# 2021_Deployment_REVB.net
KiCad netlist of a schematic drawn in EAGLE
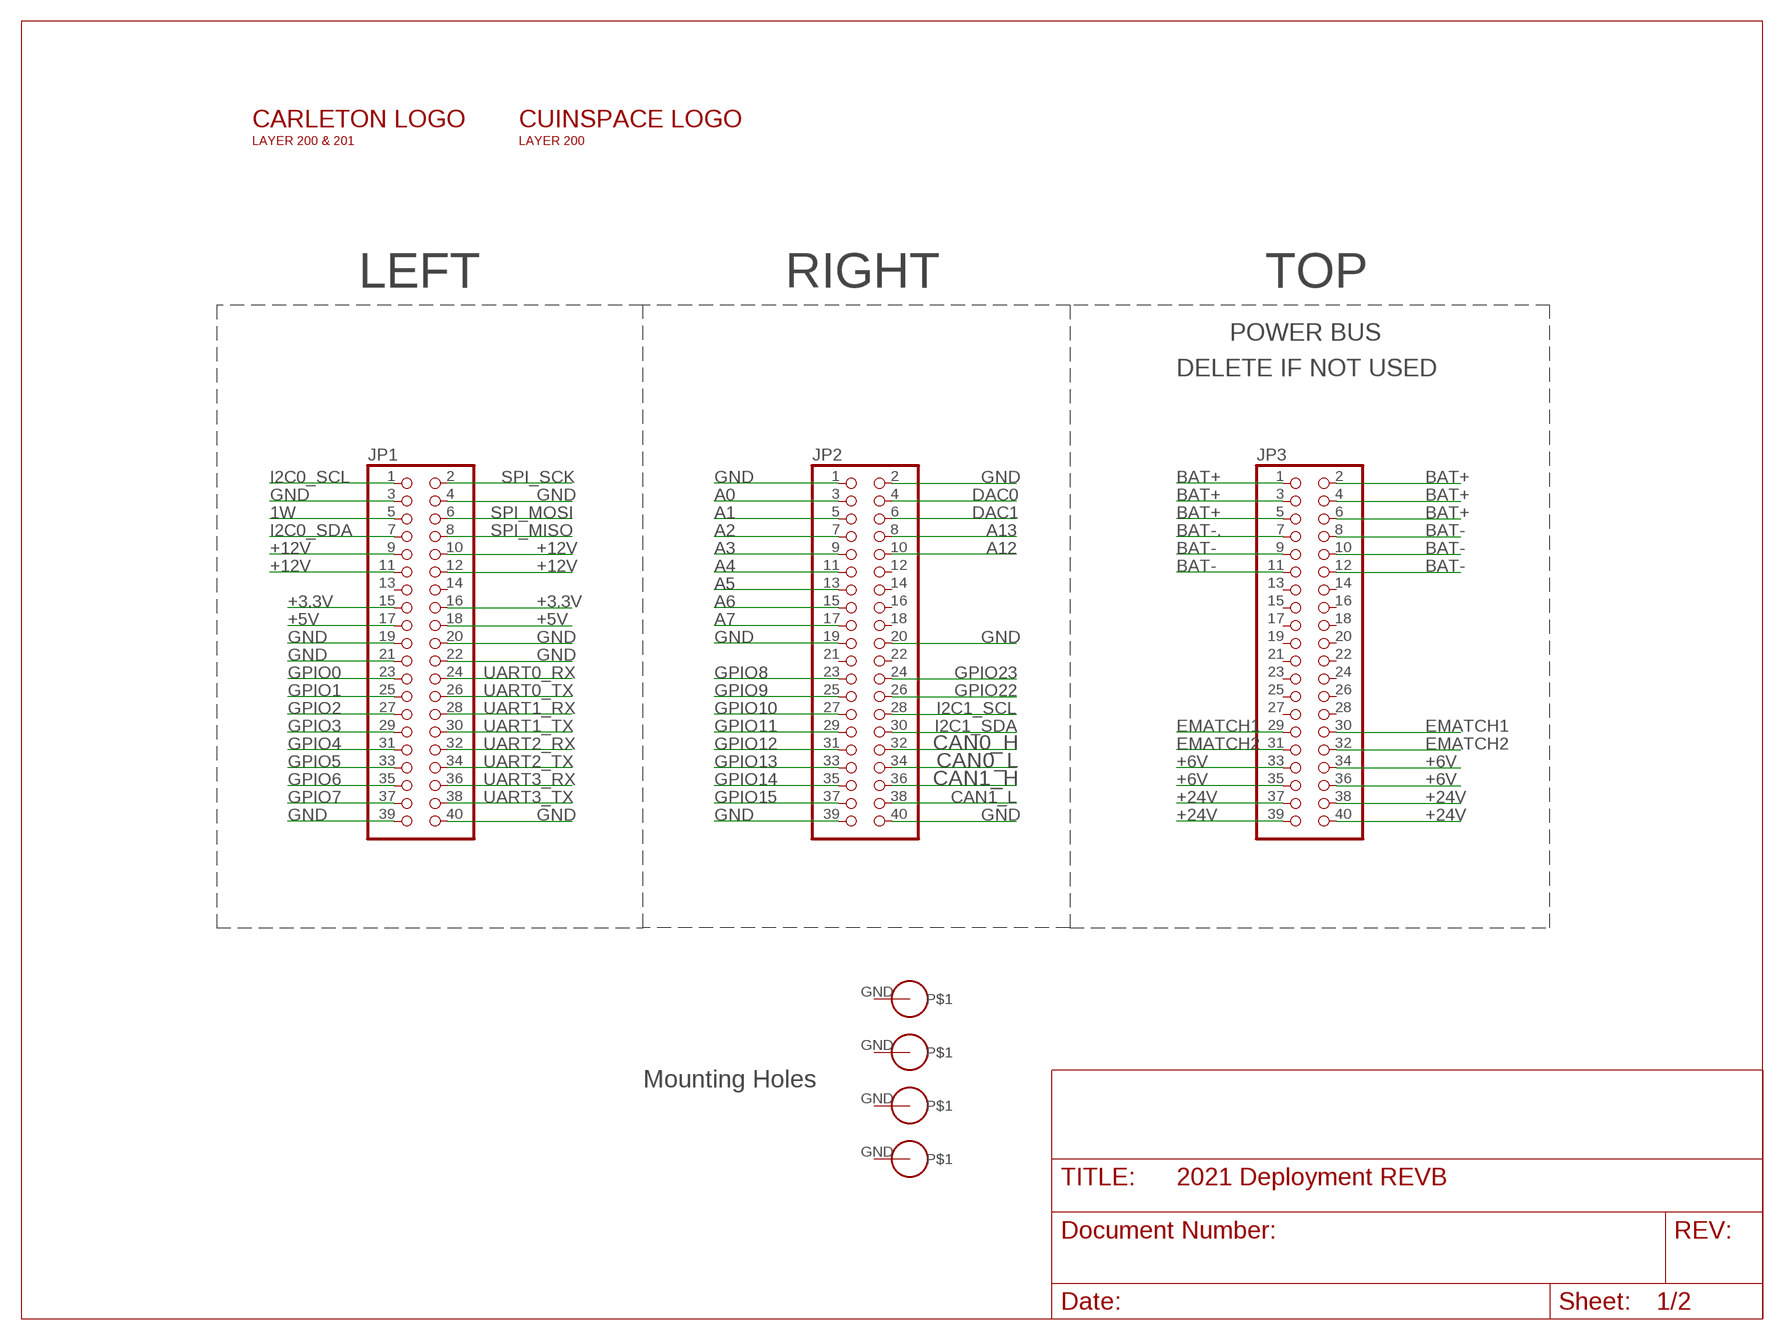
[diagram p0: schematic, sheet 1]
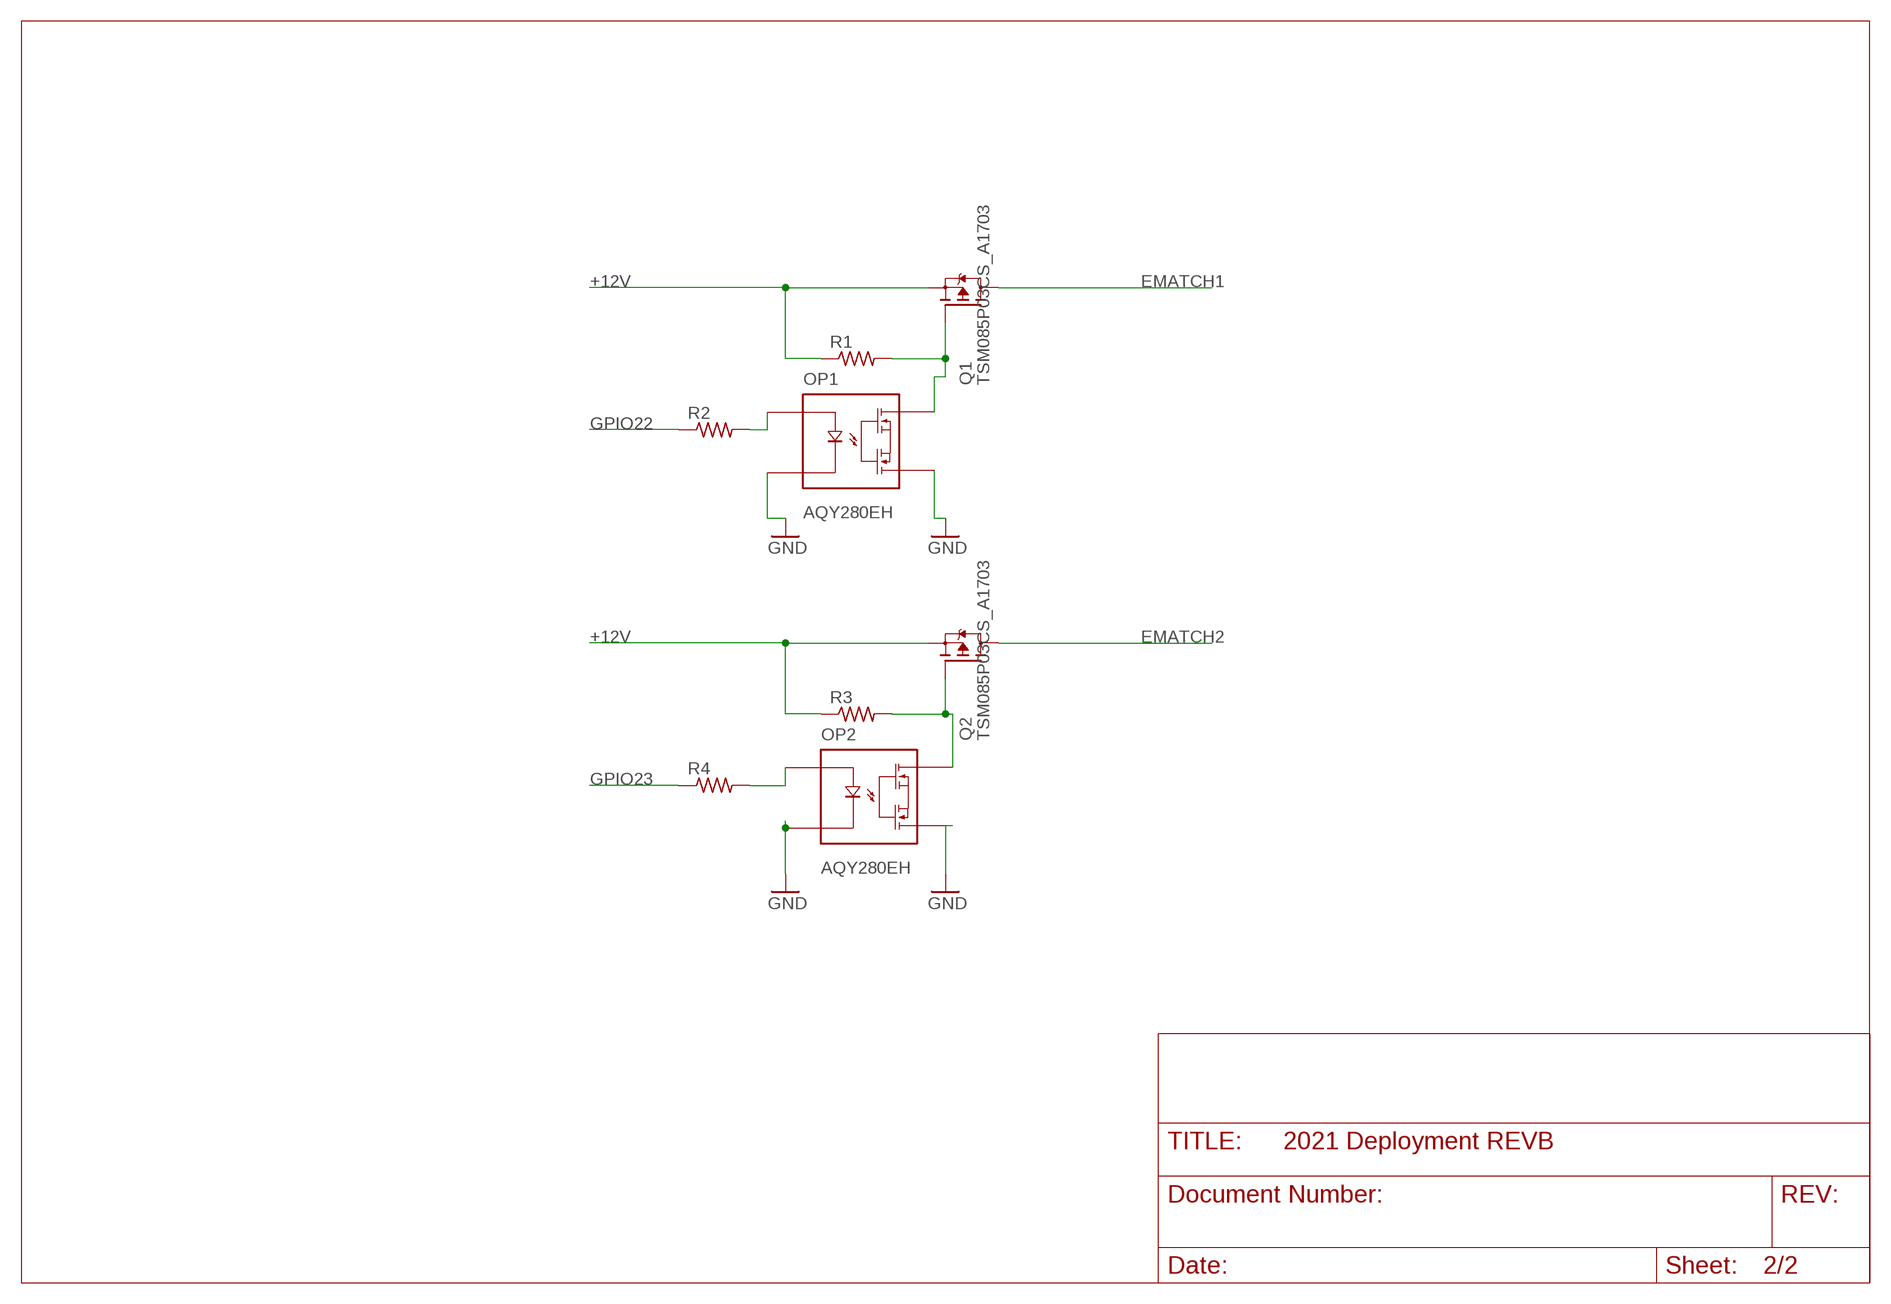
[diagram p1: schematic, sheet 2]

(export (version "E")
  (design (tool "Eeschema 10.0.6"))
  (components
    (comp (ref "OP1")
      (value "AQY280EH")
      (footprint "eagle-import:AQY280EH")
      (libsource (lib "eagle-import") (part "AQY280EH"))
    )
    (comp (ref "OP2")
      (value "AQY280EH")
      (footprint "eagle-import:AQY280EH")
      (libsource (lib "eagle-import") (part "AQY280EH"))
    )
    (comp (ref "Q1")
      (value "TSM085P03CS_A1703")
      (footprint "eagle-import:TSM085P03CS_A1703")
      (libsource (lib "eagle-import") (part "TSM085P03CS_A1703"))
    )
    (comp (ref "Q2")
      (value "TSM085P03CS_A1703")
      (footprint "eagle-import:TSM085P03CS_A1703")
      (libsource (lib "eagle-import") (part "TSM085P03CS_A1703"))
    )
    (comp (ref "R1")
      (value "R-US_R0805")
      (footprint "eagle-import:R0805")
      (libsource (lib "eagle-import") (part "R-US_R0805"))
    )
    (comp (ref "R2")
      (value "R-US_R0805")
      (footprint "eagle-import:R0805")
      (libsource (lib "eagle-import") (part "R-US_R0805"))
    )
    (comp (ref "R3")
      (value "R-US_R0805")
      (footprint "eagle-import:R0805")
      (libsource (lib "eagle-import") (part "R-US_R0805"))
    )
    (comp (ref "R4")
      (value "R-US_R0805")
      (footprint "eagle-import:R0805")
      (libsource (lib "eagle-import") (part "R-US_R0805"))
    )
    (comp (ref "$$U$1")
      (value "PS/104-MOUNTING-HOLE")
      (footprint "eagle-import:PC_104-MOUNTING-HOLE")
      (libsource (lib "eagle-import") (part "PS/104-MOUNTING-HOLE"))
    )
    (comp (ref "JP1")
      (value "PINHD-2X20")
      (footprint "eagle-import:2X20")
      (libsource (lib "eagle-import") (part "PINHD-2X20"))
    )
    (comp (ref "JP2")
      (value "PINHD-2X20")
      (footprint "eagle-import:2X20")
      (libsource (lib "eagle-import") (part "PINHD-2X20"))
    )
    (comp (ref "JP3")
      (value "PINHD-2X20")
      (footprint "eagle-import:2X20")
      (libsource (lib "eagle-import") (part "PINHD-2X20"))
    )
    (comp (ref "U$1")
      (value "PS/104-MOUNTING-HOLE")
      (footprint "eagle-import:PC_104-MOUNTING-HOLE")
      (libsource (lib "eagle-import") (part "PS/104-MOUNTING-HOLE"))
    )
    (comp (ref "U$2")
      (value "PS/104-MOUNTING-HOLE")
      (footprint "eagle-import:PC_104-MOUNTING-HOLE")
      (libsource (lib "eagle-import") (part "PS/104-MOUNTING-HOLE"))
    )
    (comp (ref "U$3")
      (value "PS/104-MOUNTING-HOLE")
      (footprint "eagle-import:PC_104-MOUNTING-HOLE")
      (libsource (lib "eagle-import") (part "PS/104-MOUNTING-HOLE"))
    )
    (comp (ref "U$4")
      (value "CARLETON3CM")
      (footprint "eagle-import:CARLETONU_3CM")
      (libsource (lib "eagle-import") (part "CARLETON3CM"))
    )
    (comp (ref "U$6")
      (value "INSPACE3CM_L")
      (footprint "eagle-import:INSPACE_3CM_LETTERS")
      (libsource (lib "eagle-import") (part "INSPACE3CM_L"))
    )
  )
  (nets
    (net (code "1") (name "+3.3V") (class "Default")
      (node (ref "JP1") (pin "15") (pinfunction "15_15") (pintype "passive"))
      (node (ref "JP1") (pin "16") (pinfunction "16_16") (pintype "passive"))
    )
    (net (code "2") (name "+5V") (class "Default")
      (node (ref "JP1") (pin "17") (pinfunction "17_17") (pintype "passive"))
      (node (ref "JP1") (pin "18") (pinfunction "18_18") (pintype "passive"))
    )
    (net (code "3") (name "+6V") (class "Default")
      (node (ref "JP3") (pin "33") (pinfunction "33_33") (pintype "passive"))
      (node (ref "JP3") (pin "34") (pinfunction "34_34") (pintype "passive"))
      (node (ref "JP3") (pin "35") (pinfunction "35_35") (pintype "passive"))
      (node (ref "JP3") (pin "36") (pinfunction "36_36") (pintype "passive"))
    )
    (net (code "4") (name "+12V") (class "Default")
      (node (ref "JP1") (pin "10") (pinfunction "10_10") (pintype "passive"))
      (node (ref "JP1") (pin "11") (pinfunction "11_11") (pintype "passive"))
      (node (ref "JP1") (pin "12") (pinfunction "12_12") (pintype "passive"))
      (node (ref "JP1") (pin "9") (pinfunction "9_9") (pintype "passive"))
      (node (ref "Q1") (pin "PIN1") (pinfunction "S_PIN1") (pintype "passive"))
      (node (ref "Q1") (pin "PIN2") (pinfunction "S_PIN2") (pintype "passive"))
      (node (ref "Q1") (pin "PIN3") (pinfunction "S_PIN3") (pintype "passive"))
      (node (ref "Q2") (pin "PIN1") (pinfunction "S_PIN1") (pintype "passive"))
      (node (ref "Q2") (pin "PIN2") (pinfunction "S_PIN2") (pintype "passive"))
      (node (ref "Q2") (pin "PIN3") (pinfunction "S_PIN3") (pintype "passive"))
      (node (ref "R1") (pin "1") (pinfunction "1_1") (pintype "passive"))
      (node (ref "R3") (pin "1") (pinfunction "1_1") (pintype "passive"))
    )
    (net (code "5") (name "+24V") (class "Default")
      (node (ref "JP3") (pin "37") (pinfunction "37_37") (pintype "passive"))
      (node (ref "JP3") (pin "38") (pinfunction "38_38") (pintype "passive"))
      (node (ref "JP3") (pin "39") (pinfunction "39_39") (pintype "passive"))
      (node (ref "JP3") (pin "40") (pinfunction "40_40") (pintype "passive"))
    )
    (net (code "6") (name "1W") (class "Default")
      (node (ref "JP1") (pin "5") (pinfunction "5_5") (pintype "passive"))
    )
    (net (code "7") (name "A0") (class "Default")
      (node (ref "JP2") (pin "3") (pinfunction "3_3") (pintype "passive"))
    )
    (net (code "8") (name "A1") (class "Default")
      (node (ref "JP2") (pin "5") (pinfunction "5_5") (pintype "passive"))
    )
    (net (code "9") (name "A2") (class "Default")
      (node (ref "JP2") (pin "7") (pinfunction "7_7") (pintype "passive"))
    )
    (net (code "10") (name "A3") (class "Default")
      (node (ref "JP2") (pin "9") (pinfunction "9_9") (pintype "passive"))
    )
    (net (code "11") (name "A4") (class "Default")
      (node (ref "JP2") (pin "11") (pinfunction "11_11") (pintype "passive"))
    )
    (net (code "12") (name "A5") (class "Default")
      (node (ref "JP2") (pin "13") (pinfunction "13_13") (pintype "passive"))
    )
    (net (code "13") (name "A6") (class "Default")
      (node (ref "JP2") (pin "15") (pinfunction "15_15") (pintype "passive"))
    )
    (net (code "14") (name "A7") (class "Default")
      (node (ref "JP2") (pin "17") (pinfunction "17_17") (pintype "passive"))
    )
    (net (code "15") (name "A12") (class "Default")
      (node (ref "JP2") (pin "10") (pinfunction "10_10") (pintype "passive"))
    )
    (net (code "16") (name "A13") (class "Default")
      (node (ref "JP2") (pin "8") (pinfunction "8_8") (pintype "passive"))
    )
    (net (code "17") (name "BAT+") (class "Default")
      (node (ref "JP3") (pin "1") (pinfunction "1_1") (pintype "passive"))
      (node (ref "JP3") (pin "2") (pinfunction "2_2") (pintype "passive"))
      (node (ref "JP3") (pin "3") (pinfunction "3_3") (pintype "passive"))
      (node (ref "JP3") (pin "4") (pinfunction "4_4") (pintype "passive"))
      (node (ref "JP3") (pin "5") (pinfunction "5_5") (pintype "passive"))
      (node (ref "JP3") (pin "6") (pinfunction "6_6") (pintype "passive"))
    )
    (net (code "18") (name "BAT-") (class "Default")
      (node (ref "JP3") (pin "10") (pinfunction "10_10") (pintype "passive"))
      (node (ref "JP3") (pin "11") (pinfunction "11_11") (pintype "passive"))
      (node (ref "JP3") (pin "12") (pinfunction "12_12") (pintype "passive"))
      (node (ref "JP3") (pin "8") (pinfunction "8_8") (pintype "passive"))
      (node (ref "JP3") (pin "9") (pinfunction "9_9") (pintype "passive"))
    )
    (net (code "19") (name "BAT-.") (class "Default")
      (node (ref "JP3") (pin "7") (pinfunction "7_7") (pintype "passive"))
    )
    (net (code "20") (name "CAN0_H") (class "Default")
      (node (ref "JP2") (pin "32") (pinfunction "32_32") (pintype "passive"))
    )
    (net (code "21") (name "CAN0_L") (class "Default")
      (node (ref "JP2") (pin "34") (pinfunction "34_34") (pintype "passive"))
    )
    (net (code "22") (name "CAN1_H") (class "Default")
      (node (ref "JP2") (pin "36") (pinfunction "36_36") (pintype "passive"))
    )
    (net (code "23") (name "CAN1_L") (class "Default")
      (node (ref "JP2") (pin "38") (pinfunction "38_38") (pintype "passive"))
    )
    (net (code "24") (name "DAC0") (class "Default")
      (node (ref "JP2") (pin "4") (pinfunction "4_4") (pintype "passive"))
    )
    (net (code "25") (name "DAC1") (class "Default")
      (node (ref "JP2") (pin "6") (pinfunction "6_6") (pintype "passive"))
    )
    (net (code "26") (name "EMATCH1") (class "Default")
      (node (ref "JP3") (pin "29") (pinfunction "29_29") (pintype "passive"))
      (node (ref "JP3") (pin "30") (pinfunction "30_30") (pintype "passive"))
      (node (ref "Q1") (pin "PIN5") (pinfunction "D_PIN5") (pintype "passive"))
      (node (ref "Q1") (pin "PIN6") (pinfunction "D_PIN6") (pintype "passive"))
      (node (ref "Q1") (pin "PIN7") (pinfunction "D_PIN7") (pintype "passive"))
      (node (ref "Q1") (pin "PIN8") (pinfunction "D_PIN8") (pintype "passive"))
    )
    (net (code "27") (name "EMATCH2") (class "Default")
      (node (ref "JP3") (pin "31") (pinfunction "31_31") (pintype "passive"))
      (node (ref "JP3") (pin "32") (pinfunction "32_32") (pintype "passive"))
      (node (ref "Q2") (pin "PIN5") (pinfunction "D_PIN5") (pintype "passive"))
      (node (ref "Q2") (pin "PIN6") (pinfunction "D_PIN6") (pintype "passive"))
      (node (ref "Q2") (pin "PIN7") (pinfunction "D_PIN7") (pintype "passive"))
      (node (ref "Q2") (pin "PIN8") (pinfunction "D_PIN8") (pintype "passive"))
    )
    (net (code "28") (name "GND") (class "Default")
      (node (ref "JP1") (pin "19") (pinfunction "19_19") (pintype "passive"))
      (node (ref "JP1") (pin "20") (pinfunction "20_20") (pintype "passive"))
      (node (ref "JP1") (pin "21") (pinfunction "21_21") (pintype "passive"))
      (node (ref "JP1") (pin "22") (pinfunction "22_22") (pintype "passive"))
      (node (ref "JP1") (pin "3") (pinfunction "3_3") (pintype "passive"))
      (node (ref "JP1") (pin "39") (pinfunction "39_39") (pintype "passive"))
      (node (ref "JP1") (pin "4") (pinfunction "4_4") (pintype "passive"))
      (node (ref "JP1") (pin "40") (pinfunction "40_40") (pintype "passive"))
      (node (ref "JP2") (pin "1") (pinfunction "1_1") (pintype "passive"))
      (node (ref "JP2") (pin "19") (pinfunction "19_19") (pintype "passive"))
      (node (ref "JP2") (pin "2") (pinfunction "2_2") (pintype "passive"))
      (node (ref "JP2") (pin "20") (pinfunction "20_20") (pintype "passive"))
      (node (ref "JP2") (pin "39") (pinfunction "39_39") (pintype "passive"))
      (node (ref "JP2") (pin "40") (pinfunction "40_40") (pintype "passive"))
      (node (ref "OP1") (pin "PIN2") (pinfunction "C_PIN2") (pintype "bidirectional"))
      (node (ref "OP1") (pin "PIN3") (pinfunction "BOTTOM_PIN3") (pintype "bidirectional"))
      (node (ref "OP2") (pin "PIN2") (pinfunction "C_PIN2") (pintype "bidirectional"))
      (node (ref "OP2") (pin "PIN3") (pinfunction "BOTTOM_PIN3") (pintype "bidirectional"))
    )
    (net (code "29") (name "GPIO0") (class "Default")
      (node (ref "JP1") (pin "23") (pinfunction "23_23") (pintype "passive"))
    )
    (net (code "30") (name "GPIO1") (class "Default")
      (node (ref "JP1") (pin "25") (pinfunction "25_25") (pintype "passive"))
    )
    (net (code "31") (name "GPIO2") (class "Default")
      (node (ref "JP1") (pin "27") (pinfunction "27_27") (pintype "passive"))
    )
    (net (code "32") (name "GPIO3") (class "Default")
      (node (ref "JP1") (pin "29") (pinfunction "29_29") (pintype "passive"))
    )
    (net (code "33") (name "GPIO4") (class "Default")
      (node (ref "JP1") (pin "31") (pinfunction "31_31") (pintype "passive"))
    )
    (net (code "34") (name "GPIO5") (class "Default")
      (node (ref "JP1") (pin "33") (pinfunction "33_33") (pintype "passive"))
    )
    (net (code "35") (name "GPIO6") (class "Default")
      (node (ref "JP1") (pin "35") (pinfunction "35_35") (pintype "passive"))
    )
    (net (code "36") (name "GPIO7") (class "Default")
      (node (ref "JP1") (pin "37") (pinfunction "37_37") (pintype "passive"))
    )
    (net (code "37") (name "GPIO8") (class "Default")
      (node (ref "JP2") (pin "23") (pinfunction "23_23") (pintype "passive"))
    )
    (net (code "38") (name "GPIO9") (class "Default")
      (node (ref "JP2") (pin "25") (pinfunction "25_25") (pintype "passive"))
    )
    (net (code "39") (name "GPIO10") (class "Default")
      (node (ref "JP2") (pin "27") (pinfunction "27_27") (pintype "passive"))
    )
    (net (code "40") (name "GPIO11") (class "Default")
      (node (ref "JP2") (pin "29") (pinfunction "29_29") (pintype "passive"))
    )
    (net (code "41") (name "GPIO12") (class "Default")
      (node (ref "JP2") (pin "31") (pinfunction "31_31") (pintype "passive"))
    )
    (net (code "42") (name "GPIO13") (class "Default")
      (node (ref "JP2") (pin "33") (pinfunction "33_33") (pintype "passive"))
    )
    (net (code "43") (name "GPIO14") (class "Default")
      (node (ref "JP2") (pin "35") (pinfunction "35_35") (pintype "passive"))
    )
    (net (code "44") (name "GPIO15") (class "Default")
      (node (ref "JP2") (pin "37") (pinfunction "37_37") (pintype "passive"))
    )
    (net (code "45") (name "GPIO22") (class "Default")
      (node (ref "JP2") (pin "26") (pinfunction "26_26") (pintype "passive"))
      (node (ref "R2") (pin "1") (pinfunction "1_1") (pintype "passive"))
    )
    (net (code "46") (name "GPIO23") (class "Default")
      (node (ref "JP2") (pin "24") (pinfunction "24_24") (pintype "passive"))
      (node (ref "R4") (pin "1") (pinfunction "1_1") (pintype "passive"))
    )
    (net (code "47") (name "I2C0_SCL") (class "Default")
      (node (ref "JP1") (pin "1") (pinfunction "1_1") (pintype "passive"))
    )
    (net (code "48") (name "I2C0_SDA") (class "Default")
      (node (ref "JP1") (pin "7") (pinfunction "7_7") (pintype "passive"))
    )
    (net (code "49") (name "I2C1_SCL") (class "Default")
      (node (ref "JP2") (pin "28") (pinfunction "28_28") (pintype "passive"))
    )
    (net (code "50") (name "I2C1_SDA") (class "Default")
      (node (ref "JP2") (pin "30") (pinfunction "30_30") (pintype "passive"))
    )
    (net (code "51") (name "Net-(OP1-A)") (class "Default")
      (node (ref "OP1") (pin "PIN1") (pinfunction "A_PIN1") (pintype "bidirectional"))
      (node (ref "R2") (pin "2") (pinfunction "2_2") (pintype "passive"))
    )
    (net (code "52") (name "Net-(OP1-TOP)") (class "Default")
      (node (ref "OP1") (pin "PIN4") (pinfunction "TOP_PIN4") (pintype "bidirectional"))
      (node (ref "Q1") (pin "PIN4") (pinfunction "G_PIN4") (pintype "passive"))
      (node (ref "R1") (pin "2") (pinfunction "2_2") (pintype "passive"))
    )
    (net (code "53") (name "Net-(OP2-A)") (class "Default")
      (node (ref "OP2") (pin "PIN1") (pinfunction "A_PIN1") (pintype "bidirectional"))
      (node (ref "R4") (pin "2") (pinfunction "2_2") (pintype "passive"))
    )
    (net (code "54") (name "Net-(OP2-TOP)") (class "Default")
      (node (ref "OP2") (pin "PIN4") (pinfunction "TOP_PIN4") (pintype "bidirectional"))
      (node (ref "Q2") (pin "PIN4") (pinfunction "G_PIN4") (pintype "passive"))
      (node (ref "R3") (pin "2") (pinfunction "2_2") (pintype "passive"))
    )
    (net (code "55") (name "SPI_MISO") (class "Default")
      (node (ref "JP1") (pin "8") (pinfunction "8_8") (pintype "passive"))
    )
    (net (code "56") (name "SPI_MOSI") (class "Default")
      (node (ref "JP1") (pin "6") (pinfunction "6_6") (pintype "passive"))
    )
    (net (code "57") (name "SPI_SCK") (class "Default")
      (node (ref "JP1") (pin "2") (pinfunction "2_2") (pintype "passive"))
    )
    (net (code "58") (name "UART0_RX") (class "Default")
      (node (ref "JP1") (pin "24") (pinfunction "24_24") (pintype "passive"))
    )
    (net (code "59") (name "UART0_TX") (class "Default")
      (node (ref "JP1") (pin "26") (pinfunction "26_26") (pintype "passive"))
    )
    (net (code "60") (name "UART1_RX") (class "Default")
      (node (ref "JP1") (pin "28") (pinfunction "28_28") (pintype "passive"))
    )
    (net (code "61") (name "UART1_TX") (class "Default")
      (node (ref "JP1") (pin "30") (pinfunction "30_30") (pintype "passive"))
    )
    (net (code "62") (name "UART2_RX") (class "Default")
      (node (ref "JP1") (pin "32") (pinfunction "32_32") (pintype "passive"))
    )
    (net (code "63") (name "UART2_TX") (class "Default")
      (node (ref "JP1") (pin "34") (pinfunction "34_34") (pintype "passive"))
    )
    (net (code "64") (name "UART3_RX") (class "Default")
      (node (ref "JP1") (pin "36") (pinfunction "36_36") (pintype "passive"))
    )
    (net (code "65") (name "UART3_TX") (class "Default")
      (node (ref "JP1") (pin "38") (pinfunction "38_38") (pintype "passive"))
    )
    (net (code "66") (name "unconnected-($$U$1-P$1-PadGND)") (class "Default")
      (node (ref "$$U$1") (pin "GND") (pinfunction "P$1_GND") (pintype "bidirectional"))
    )
    (net (code "67") (name "unconnected-(JP1-Pad13)") (class "Default")
      (node (ref "JP1") (pin "13") (pinfunction "13_13") (pintype "passive"))
    )
    (net (code "68") (name "unconnected-(JP1-Pad14)") (class "Default")
      (node (ref "JP1") (pin "14") (pinfunction "14_14") (pintype "passive"))
    )
    (net (code "69") (name "unconnected-(JP2-Pad12)") (class "Default")
      (node (ref "JP2") (pin "12") (pinfunction "12_12") (pintype "passive"))
    )
    (net (code "70") (name "unconnected-(JP2-Pad14)") (class "Default")
      (node (ref "JP2") (pin "14") (pinfunction "14_14") (pintype "passive"))
    )
    (net (code "71") (name "unconnected-(JP2-Pad16)") (class "Default")
      (node (ref "JP2") (pin "16") (pinfunction "16_16") (pintype "passive"))
    )
    (net (code "72") (name "unconnected-(JP2-Pad18)") (class "Default")
      (node (ref "JP2") (pin "18") (pinfunction "18_18") (pintype "passive"))
    )
    (net (code "73") (name "unconnected-(JP2-Pad21)") (class "Default")
      (node (ref "JP2") (pin "21") (pinfunction "21_21") (pintype "passive"))
    )
    (net (code "74") (name "unconnected-(JP2-Pad22)") (class "Default")
      (node (ref "JP2") (pin "22") (pinfunction "22_22") (pintype "passive"))
    )
    (net (code "75") (name "unconnected-(JP3-Pad13)") (class "Default")
      (node (ref "JP3") (pin "13") (pinfunction "13_13") (pintype "passive"))
    )
    (net (code "76") (name "unconnected-(JP3-Pad14)") (class "Default")
      (node (ref "JP3") (pin "14") (pinfunction "14_14") (pintype "passive"))
    )
    (net (code "77") (name "unconnected-(JP3-Pad15)") (class "Default")
      (node (ref "JP3") (pin "15") (pinfunction "15_15") (pintype "passive"))
    )
    (net (code "78") (name "unconnected-(JP3-Pad16)") (class "Default")
      (node (ref "JP3") (pin "16") (pinfunction "16_16") (pintype "passive"))
    )
    (net (code "79") (name "unconnected-(JP3-Pad17)") (class "Default")
      (node (ref "JP3") (pin "17") (pinfunction "17_17") (pintype "passive"))
    )
    (net (code "80") (name "unconnected-(JP3-Pad18)") (class "Default")
      (node (ref "JP3") (pin "18") (pinfunction "18_18") (pintype "passive"))
    )
    (net (code "81") (name "unconnected-(JP3-Pad19)") (class "Default")
      (node (ref "JP3") (pin "19") (pinfunction "19_19") (pintype "passive"))
    )
    (net (code "82") (name "unconnected-(JP3-Pad20)") (class "Default")
      (node (ref "JP3") (pin "20") (pinfunction "20_20") (pintype "passive"))
    )
    (net (code "83") (name "unconnected-(JP3-Pad21)") (class "Default")
      (node (ref "JP3") (pin "21") (pinfunction "21_21") (pintype "passive"))
    )
    (net (code "84") (name "unconnected-(JP3-Pad22)") (class "Default")
      (node (ref "JP3") (pin "22") (pinfunction "22_22") (pintype "passive"))
    )
    (net (code "85") (name "unconnected-(JP3-Pad23)") (class "Default")
      (node (ref "JP3") (pin "23") (pinfunction "23_23") (pintype "passive"))
    )
    (net (code "86") (name "unconnected-(JP3-Pad24)") (class "Default")
      (node (ref "JP3") (pin "24") (pinfunction "24_24") (pintype "passive"))
    )
    (net (code "87") (name "unconnected-(JP3-Pad25)") (class "Default")
      (node (ref "JP3") (pin "25") (pinfunction "25_25") (pintype "passive"))
    )
    (net (code "88") (name "unconnected-(JP3-Pad26)") (class "Default")
      (node (ref "JP3") (pin "26") (pinfunction "26_26") (pintype "passive"))
    )
    (net (code "89") (name "unconnected-(JP3-Pad27)") (class "Default")
      (node (ref "JP3") (pin "27") (pinfunction "27_27") (pintype "passive"))
    )
    (net (code "90") (name "unconnected-(JP3-Pad28)") (class "Default")
      (node (ref "JP3") (pin "28") (pinfunction "28_28") (pintype "passive"))
    )
    (net (code "91") (name "unconnected-(U$1-P$1-PadGND)") (class "Default")
      (node (ref "U$1") (pin "GND") (pinfunction "P$1_GND") (pintype "bidirectional"))
    )
    (net (code "92") (name "unconnected-(U$2-P$1-PadGND)") (class "Default")
      (node (ref "U$2") (pin "GND") (pinfunction "P$1_GND") (pintype "bidirectional"))
    )
    (net (code "93") (name "unconnected-(U$3-P$1-PadGND)") (class "Default")
      (node (ref "U$3") (pin "GND") (pinfunction "P$1_GND") (pintype "bidirectional"))
    )
  )
)
